# Do-an.net
KiCad netlist of a schematic drawn in Altium Designer
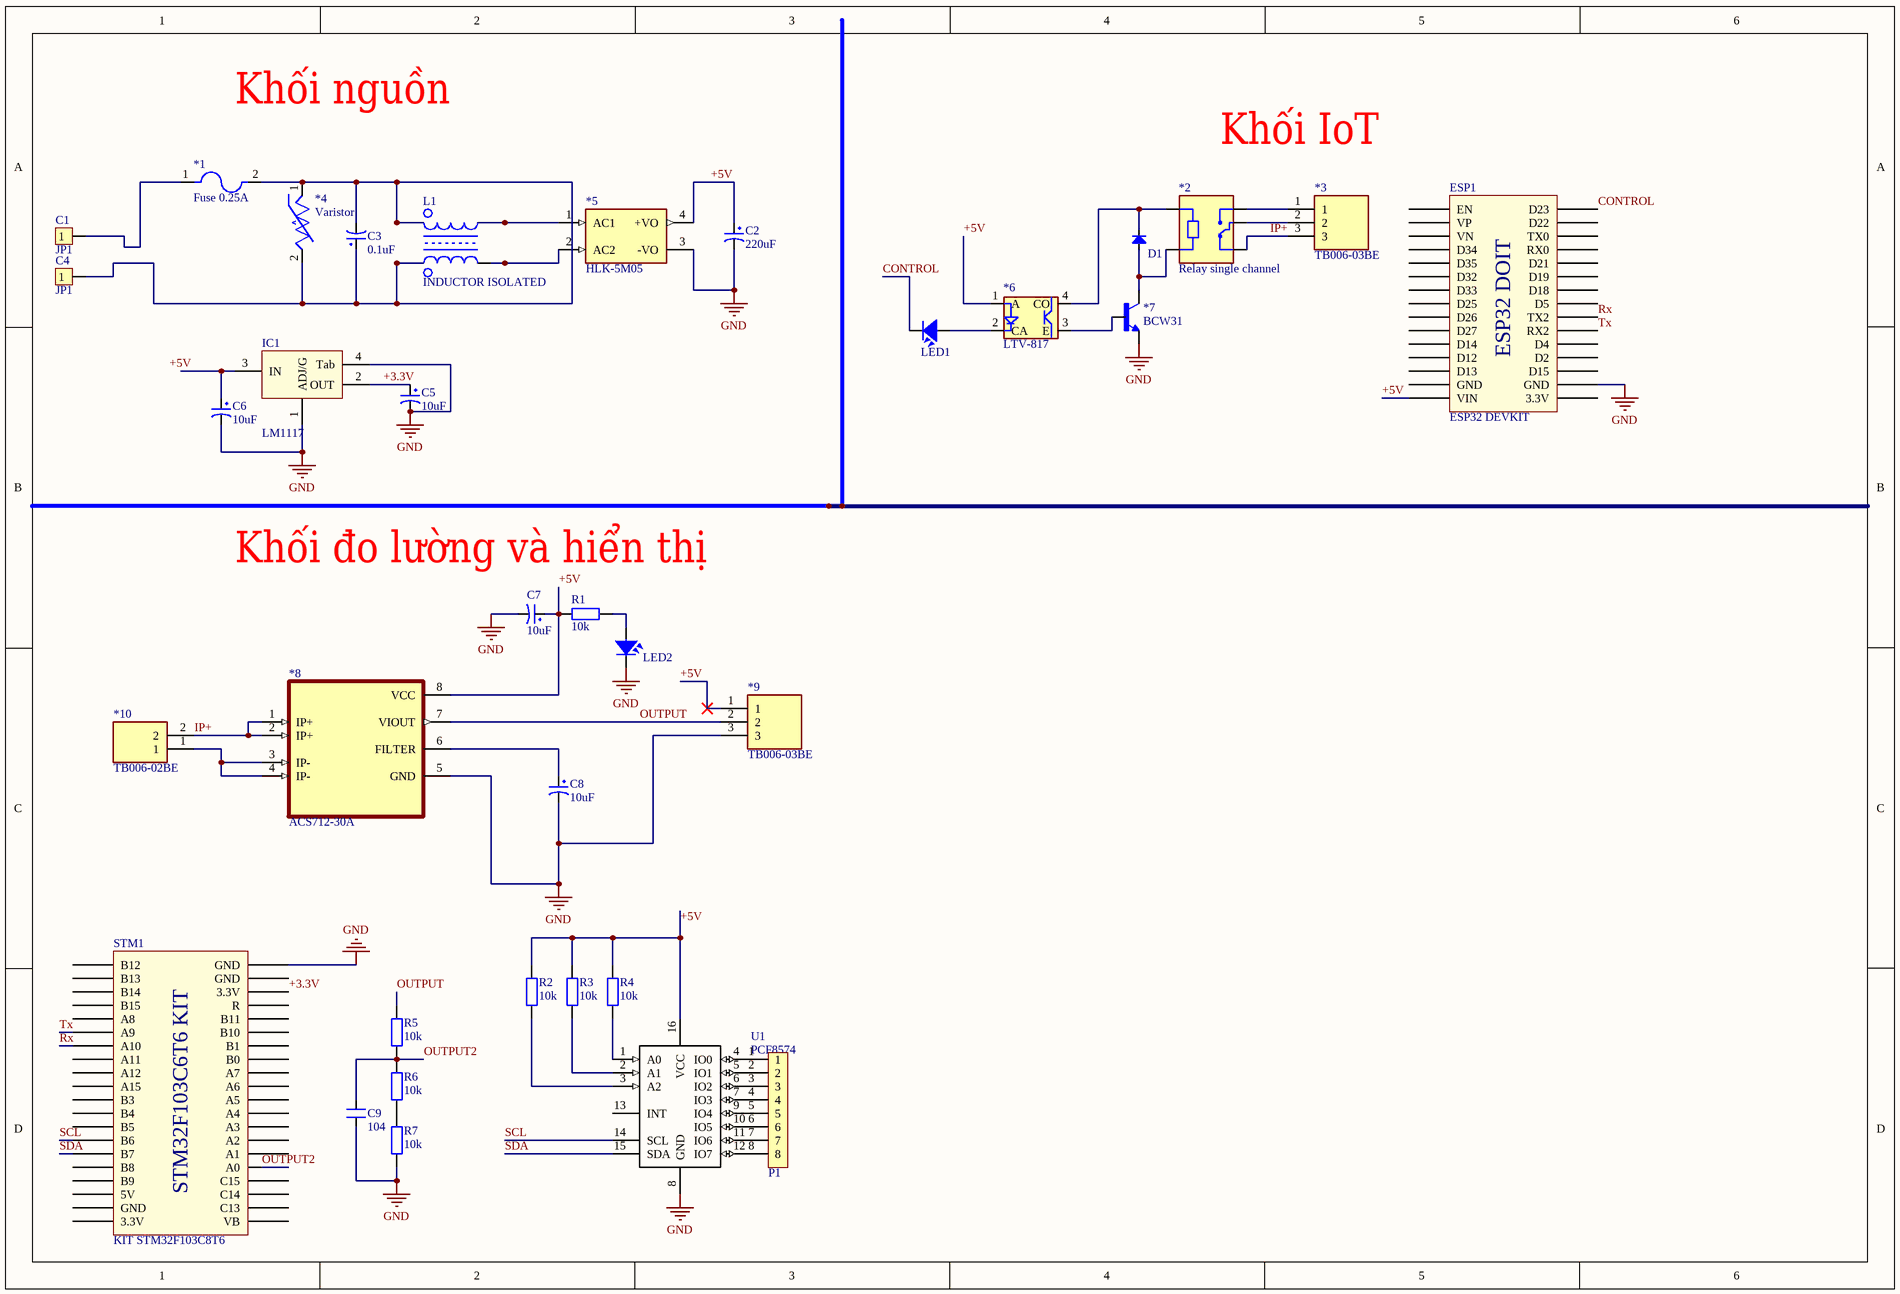
[diagram p0: Do-an.SchDoc]

(export (version "E")
  (design (tool "Eeschema 10.0.6"))
  (components
    (comp (ref "*1")
      (value "Fuse 0.25A")
      (footprint "FUSC6125X279N")
      (libsource (lib "KhanhBK_SCH_Library_2") (part "Fuse 0.25A"))
    )
    (comp (ref "*2")
      (value "Relay single channel")
      (footprint "RELAY_SRD-05VDC-SL-C")
      (libsource (lib "KhanhBK_SCH_Library_2") (part "Relay single channel"))
    )
    (comp (ref "*3")
      (value "TB006-03BE")
      (footprint "CUI_TB006 -508-03BE")
      (libsource (lib "KhanhBK_SCH_Library_2") (part "TB006-03BE"))
    )
    (comp (ref "*4")
      (value "Varistor")
      (footprint "VAR_B72220P3141K101")
      (libsource (lib "KhanhBK_SCH_Library_2") (part "Varistor"))
    )
    (comp (ref "*5")
      (value "HLK-5M05")
      (footprint "CONV_HLK-5M05")
      (libsource (lib "KhanhBK_SCH_Library_2") (part "HLK-5M05"))
    )
    (comp (ref "*6")
      (value "LTV-817")
      (footprint "LTV-817")
      (libsource (lib "KhanhBK_SCH_Library_2") (part "LTV-817"))
    )
    (comp (ref "*7")
      (value "BCW31")
      (footprint "SOT23-BEC")
      (libsource (lib "KhanhBK_SCH_Library_2") (part "BCW31"))
    )
    (comp (ref "*8")
      (value "ACS712-30A")
      (footprint "SOIC127P600X175-8N - duplicate")
      (libsource (lib "KhanhBK_SCH_Library_2") (part "ACS712-30A"))
    )
    (comp (ref "*9")
      (value "TB006-03BE")
      (footprint "CUI_TB006 -508-03BE")
      (libsource (lib "KhanhBK_SCH_Library_2") (part "TB006-03BE"))
    )
    (comp (ref "*10")
      (value "TB006-02BE")
      (footprint "CUI_TB006-508-02BE")
      (libsource (lib "KhanhBK_SCH_Library_2") (part "TB006-02BE"))
    )
    (comp (ref "C1")
      (value "JP1")
      (footprint "JP1-D1T")
      (description "WR-PHD 2.54 mm Angled Socket Header")
      (fields
        (field (name "MANUFACTURER") "Würth Elektronik eiSos GmbH")
        (field (name "PARTNO") "613002143121")
        (field (name "CREATED BY") "Karrer Zheng")
      )
      (libsource (lib "Do-an") (part "JP1"))
    )
    (comp (ref "C2")
      (value "220uF")
      (footprint "CP1.5/3.4")
      (description "Cap 100uF/35V - 470uF/16V")
      (libsource (lib "KhanhBK_SCH_Library_2") (part "CP3"))
    )
    (comp (ref "C3")
      (value "0.1uF")
      (footprint "CP1/2")
      (description "Cap P  0,1uF < 22uF , 16 - 50V")
      (libsource (lib "KhanhBK_SCH_Library_2") (part "CP1"))
    )
    (comp (ref "C4")
      (value "JP1")
      (footprint "JP1-D1T")
      (description "WR-PHD 2.54 mm Angled Socket Header")
      (fields
        (field (name "MANUFACTURER") "Würth Elektronik eiSos GmbH")
        (field (name "PARTNO") "613002143121")
        (field (name "CREATED BY") "Karrer Zheng")
      )
      (libsource (lib "KhanhBK_SCH_Library_1") (part "JP1"))
    )
    (comp (ref "C5")
      (value "10uF")
      (footprint "CP1/2")
      (description "Cap P  0,1uF < 22uF , 16 - 50V")
      (libsource (lib "KhanhBK_SCH_Library_2") (part "CP1"))
    )
    (comp (ref "C6")
      (value "10uF")
      (footprint "CP1/2")
      (description "Cap P  0,1uF < 22uF , 16 - 50V")
      (libsource (lib "KhanhBK_SCH_Library_2") (part "CP1"))
    )
    (comp (ref "C7")
      (value "10uF")
      (footprint "CP1/2")
      (description "Cap P  0,1uF < 22uF , 16 - 50V")
      (libsource (lib "") (part "CP1_1"))
    )
    (comp (ref "C8")
      (value "10uF")
      (footprint "CP1/2")
      (description "Cap P  0,1uF < 22uF , 16 - 50V")
      (libsource (lib "KhanhBK_SCH_Library_2") (part "CP1"))
    )
    (comp (ref "C9")
      (value "104")
      (footprint "CN2")
      (description "Cap np 104 => 105pF")
      (libsource (lib "KhanhBK_SCH_Library_2") (part "CN2"))
    )
    (comp (ref "D1")
      (value "Diode")
      (footprint "DIO-1A")
      (description "Default Diode")
      (fields (field (name "PUBLISHER") "Altium Limited"))
      (libsource (lib "KhanhBK_SCH_Library_2") (part "Diode"))
    )
    (comp (ref "ESP1")
      (value "ESP32 DEVKIT")
      (footprint "ESP32 WROOM 32 KIT")
      (libsource (lib "Module") (part "ESP32 WROOM 32 KIT"))
    )
    (comp (ref "IC1")
      (value "LM1117")
      (footprint "SOT223-4N")
      (description "3v3")
      (libsource (lib "KhanhBK_SCH_Library_2") (part "LM1117"))
    )
    (comp (ref "L1")
      (value "INDUCTOR ISOLATED")
      (footprint "INDUCTOR COMPACT")
      (libsource (lib "Devzone_SCHLib") (part "INDUCTOR ISOLATED"))
    )
    (comp (ref "LED1")
      (value "LED")
      (footprint "LED 3512")
      (libsource (lib "KhanhBK_SCH_Library_2") (part "LED SMD"))
    )
    (comp (ref "LED2")
      (value "LED")
      (footprint "LED-3MM-YELLOW")
      (description "LED Single colour Green and Red")
      (libsource (lib "KhanhBK_SCH_Library_1") (part "LED"))
    )
    (comp (ref "P1")
      (value "BIG Heager 8")
      (footprint "BIG_Header 8")
      (libsource (lib "KhanhBK_SCH_Library_2") (part "BIG_Header 8"))
    )
    (comp (ref "R1")
      (value "10k")
      (footprint "RES-1/4W")
      (description "Resistor 1/4W")
      (libsource (lib "KhanhBK_SCH_Library_2") (part "RES 1/4W"))
    )
    (comp (ref "R2")
      (value "10k")
      (footprint "RES-1/4W")
      (description "Resistor 1/4W")
      (libsource (lib "KhanhBK_SCH_Library_2") (part "RES 1/4W"))
    )
    (comp (ref "R3")
      (value "10k")
      (footprint "RES-1/4W")
      (description "Resistor 1/4W")
      (libsource (lib "KhanhBK_SCH_Library_2") (part "RES 1/4W"))
    )
    (comp (ref "R4")
      (value "10k")
      (footprint "RES-1/4W")
      (description "Resistor 1/4W")
      (libsource (lib "KhanhBK_SCH_Library_2") (part "RES 1/4W"))
    )
    (comp (ref "R5")
      (value "10k")
      (footprint "RES-1/4W")
      (description "Resistor 1/4W")
      (libsource (lib "KhanhBK_SCH_Library_2") (part "RES 1/4W"))
    )
    (comp (ref "R6")
      (value "10k")
      (footprint "RES-1/4W")
      (description "Resistor 1/4W")
      (libsource (lib "KhanhBK_SCH_Library_2") (part "RES 1/4W"))
    )
    (comp (ref "R7")
      (value "10k")
      (footprint "RES-1/4W")
      (description "Resistor 1/4W")
      (libsource (lib "KhanhBK_SCH_Library_2") (part "RES 1/4W"))
    )
    (comp (ref "STM1")
      (value "KIT STM32F103C8T6")
      (footprint "STM32F103 KIT")
      (description "KIT STM32F103C8T6 Bluepill")
      (libsource (lib "Module") (part "STM32f103 Bluepill"))
    )
    (comp (ref "U1")
      (value "PCF8574")
      (footprint "DIP16")
      (description "I2C PORT EXPANDER")
      (fields
        (field (name "MANUFACTURER PART NUMBER") "PCF8574T/3,512")
        (field (name "MANUFACTURER") "NXP Semiconductors")
      )
      (libsource (lib "KhanhBK_SCH_Library_2") (part "PCF8574"))
    )
  )
  (nets
    (net (code "1") (name "/+3.3V") (class "Default")
      (node (ref "C5") (pin "1") (pinfunction "1_1") (pintype "passive"))
      (node (ref "IC1") (pin "2") (pinfunction "OUT_2") (pintype "passive"))
      (node (ref "STM1") (pin "38") (pinfunction "3.3V_38") (pintype "passive"))
    )
    (net (code "2") (name "/+5V") (class "Default")
      (node (ref "*5") (pin "4") (pinfunction "+VO_4") (pintype "output"))
      (node (ref "*6") (pin "1") (pinfunction "A_1") (pintype "bidirectional"))
      (node (ref "*8") (pin "8") (pinfunction "VCC_8") (pintype "power_in"))
      (node (ref "*9") (pin "1") (pinfunction "1_1") (pintype "passive"))
      (node (ref "C2") (pin "1") (pinfunction "1_1") (pintype "passive"))
      (node (ref "C6") (pin "1") (pinfunction "1_1") (pintype "passive"))
      (node (ref "C7") (pin "1") (pinfunction "1_1") (pintype "passive"))
      (node (ref "ESP1") (pin "15") (pinfunction "VIN_15") (pintype "passive"))
      (node (ref "IC1") (pin "3") (pinfunction "IN_3") (pintype "passive"))
      (node (ref "R1") (pin "2") (pinfunction "2_2") (pintype "passive"))
      (node (ref "R2") (pin "2") (pinfunction "2_2") (pintype "passive"))
      (node (ref "R3") (pin "2") (pinfunction "2_2") (pintype "passive"))
      (node (ref "R4") (pin "2") (pinfunction "2_2") (pintype "passive"))
      (node (ref "U1") (pin "16") (pinfunction "VCC_16") (pintype "passive"))
    )
    (net (code "3") (name "/CONTROL") (class "Default")
      (node (ref "ESP1") (pin "30") (pinfunction "D23_30") (pintype "passive"))
      (node (ref "LED1") (pin "2") (pinfunction "2_2") (pintype "passive"))
    )
    (net (code "4") (name "/IP+") (class "Default")
      (node (ref "*10") (pin "2") (pinfunction "2_2") (pintype "passive"))
      (node (ref "*2") (pin "NC") (pinfunction "NC_NC") (pintype "passive"))
      (node (ref "*3") (pin "3") (pinfunction "3_3") (pintype "passive"))
      (node (ref "*8") (pin "1") (pinfunction "IP+_1") (pintype "input"))
      (node (ref "*8") (pin "2") (pinfunction "IP+_2") (pintype "input"))
    )
    (net (code "5") (name "/OUTPUT") (class "Default")
      (node (ref "*8") (pin "7") (pinfunction "VIOUT_7") (pintype "output"))
      (node (ref "*9") (pin "2") (pinfunction "2_2") (pintype "passive"))
      (node (ref "R5") (pin "2") (pinfunction "2_2") (pintype "passive"))
    )
    (net (code "6") (name "/OUTPUT2") (class "Default")
      (node (ref "C9") (pin "2") (pinfunction "2_2") (pintype "passive"))
      (node (ref "R5") (pin "1") (pinfunction "1_1") (pintype "passive"))
      (node (ref "R6") (pin "2") (pinfunction "2_2") (pintype "passive"))
      (node (ref "STM1") (pin "25") (pinfunction "A0_25") (pintype "passive"))
    )
    (net (code "7") (name "/Rx") (class "Default")
      (node (ref "ESP1") (pin "22") (pinfunction "TX2_22") (pintype "passive"))
      (node (ref "STM1") (pin "7") (pinfunction "A10_7") (pintype "passive"))
    )
    (net (code "8") (name "/SCL") (class "Default")
      (node (ref "STM1") (pin "14") (pinfunction "B6_14") (pintype "passive"))
      (node (ref "U1") (pin "14") (pinfunction "SCL_14") (pintype "open_collector"))
    )
    (net (code "9") (name "/SDA") (class "Default")
      (node (ref "STM1") (pin "15") (pinfunction "B7_15") (pintype "passive"))
      (node (ref "U1") (pin "15") (pinfunction "SDA_15") (pintype "open_collector"))
    )
    (net (code "10") (name "/Tx") (class "Default")
      (node (ref "ESP1") (pin "21") (pinfunction "RX2_21") (pintype "passive"))
      (node (ref "STM1") (pin "6") (pinfunction "A9_6") (pintype "passive"))
    )
    (net (code "11") (name "GND") (class "Default")
      (node (ref "*5") (pin "3") (pinfunction "-VO_3") (pintype "passive"))
      (node (ref "*7") (pin "E") (pinfunction "E_E") (pintype "passive"))
      (node (ref "*8") (pin "5") (pinfunction "GND_5") (pintype "power_in"))
      (node (ref "*9") (pin "3") (pinfunction "3_3") (pintype "passive"))
      (node (ref "C2") (pin "2") (pinfunction "2_2") (pintype "passive"))
      (node (ref "C5") (pin "2") (pinfunction "2_2") (pintype "passive"))
      (node (ref "C6") (pin "2") (pinfunction "2_2") (pintype "passive"))
      (node (ref "C7") (pin "2") (pinfunction "2_2") (pintype "passive"))
      (node (ref "C8") (pin "2") (pinfunction "2_2") (pintype "passive"))
      (node (ref "C9") (pin "1") (pinfunction "1_1") (pintype "passive"))
      (node (ref "ESP1") (pin "17") (pinfunction "GND_17") (pintype "passive"))
      (node (ref "IC1") (pin "1") (pinfunction "ADJ/G_1") (pintype "passive"))
      (node (ref "IC1") (pin "4") (pinfunction "Tab_4") (pintype "passive"))
      (node (ref "LED2") (pin "2") (pinfunction "2_2") (pintype "passive"))
      (node (ref "R7") (pin "1") (pinfunction "1_1") (pintype "passive"))
      (node (ref "STM1") (pin "40") (pinfunction "GND_40") (pintype "passive"))
      (node (ref "U1") (pin "8") (pinfunction "GND_8") (pintype "power_in"))
    )
    (net (code "12") (name "Net-(*1-Pad1)") (class "Default")
      (node (ref "*1") (pin "1") (pinfunction "1_1") (pintype "passive"))
      (node (ref "C1") (pin "1") (pinfunction "1_1") (pintype "passive"))
    )
    (net (code "13") (name "Net-(*1-Pad2)") (class "Default")
      (node (ref "*1") (pin "2") (pinfunction "2_2") (pintype "passive"))
      (node (ref "*4") (pin "1") (pinfunction "1_1") (pintype "passive"))
      (node (ref "*4") (pin "2") (pinfunction "2_2") (pintype "passive"))
      (node (ref "C3") (pin "1") (pinfunction "1_1") (pintype "passive"))
      (node (ref "C3") (pin "2") (pinfunction "2_2") (pintype "passive"))
      (node (ref "C4") (pin "1") (pinfunction "1_1") (pintype "passive"))
      (node (ref "L1") (pin "1") (pinfunction "1_1") (pintype "passive"))
      (node (ref "L1") (pin "3") (pinfunction "3_3") (pintype "passive"))
    )
    (net (code "14") (name "Net-(*2-PadCOM)") (class "Default")
      (node (ref "*2") (pin "COM") (pinfunction "COM_COM") (pintype "passive"))
      (node (ref "*3") (pin "2") (pinfunction "2_2") (pintype "passive"))
    )
    (net (code "15") (name "Net-(*2-PadNO)") (class "Default")
      (node (ref "*2") (pin "NO") (pinfunction "NO_NO") (pintype "passive"))
      (node (ref "*3") (pin "1") (pinfunction "1_1") (pintype "passive"))
    )
    (net (code "16") (name "Net-(*5-AC1)") (class "Default")
      (node (ref "*5") (pin "1") (pinfunction "AC1_1") (pintype "input"))
      (node (ref "L1") (pin "4") (pinfunction "4_4") (pintype "passive"))
    )
    (net (code "17") (name "Net-(*5-AC2)") (class "Default")
      (node (ref "*5") (pin "2") (pinfunction "AC2_2") (pintype "input"))
      (node (ref "L1") (pin "2") (pinfunction "2_2") (pintype "passive"))
    )
    (net (code "18") (name "Net-(*6-CA)") (class "Default")
      (node (ref "*6") (pin "2") (pinfunction "CA_2") (pintype "bidirectional"))
      (node (ref "LED1") (pin "1") (pinfunction "1_1") (pintype "passive"))
    )
    (net (code "19") (name "Net-(*6-CO)") (class "Default")
      (node (ref "*2") (pin "A1") (pinfunction "A1_A1") (pintype "passive"))
      (node (ref "*6") (pin "4") (pinfunction "CO_4") (pintype "bidirectional"))
      (node (ref "D1") (pin "2") (pinfunction "K_2") (pintype "passive"))
    )
    (net (code "20") (name "Net-(*6-E)") (class "Default")
      (node (ref "*6") (pin "3") (pinfunction "E_3") (pintype "bidirectional"))
      (node (ref "*7") (pin "B") (pinfunction "B_B") (pintype "passive"))
    )
    (net (code "21") (name "Net-(*8-FILTER)") (class "Default")
      (node (ref "*8") (pin "6") (pinfunction "FILTER_6") (pintype "passive"))
      (node (ref "C8") (pin "1") (pinfunction "1_1") (pintype "passive"))
    )
    (net (code "22") (name "Net-(*10-Pad1)") (class "Default")
      (node (ref "*10") (pin "1") (pinfunction "1_1") (pintype "passive"))
      (node (ref "*8") (pin "3") (pinfunction "IP-_3") (pintype "input"))
      (node (ref "*8") (pin "4") (pinfunction "IP-_4") (pintype "input"))
    )
    (net (code "23") (name "Net-(D1-A)") (class "Default")
      (node (ref "*2") (pin "A2") (pinfunction "A2_A2") (pintype "passive"))
      (node (ref "*7") (pin "C") (pinfunction "C_C") (pintype "passive"))
      (node (ref "D1") (pin "1") (pinfunction "A_1") (pintype "passive"))
    )
    (net (code "24") (name "Net-(LED2-Pad1)") (class "Default")
      (node (ref "LED2") (pin "1") (pinfunction "1_1") (pintype "passive"))
      (node (ref "R1") (pin "1") (pinfunction "1_1") (pintype "passive"))
    )
    (net (code "25") (name "Net-(R6-Pad1)") (class "Default")
      (node (ref "R6") (pin "1") (pinfunction "1_1") (pintype "passive"))
      (node (ref "R7") (pin "2") (pinfunction "2_2") (pintype "passive"))
    )
    (net (code "26") (name "Net-(U1-A0)") (class "Default")
      (node (ref "R4") (pin "1") (pinfunction "1_1") (pintype "passive"))
      (node (ref "U1") (pin "1") (pinfunction "A0_1") (pintype "input"))
    )
    (net (code "27") (name "Net-(U1-A1)") (class "Default")
      (node (ref "R3") (pin "1") (pinfunction "1_1") (pintype "passive"))
      (node (ref "U1") (pin "2") (pinfunction "A1_2") (pintype "input"))
    )
    (net (code "28") (name "Net-(U1-A2)") (class "Default")
      (node (ref "R2") (pin "1") (pinfunction "1_1") (pintype "passive"))
      (node (ref "U1") (pin "3") (pinfunction "A2_3") (pintype "input"))
    )
    (net (code "29") (name "Net-(U1-IO0)") (class "Default")
      (node (ref "P1") (pin "1") (pinfunction "1_1") (pintype "passive"))
      (node (ref "U1") (pin "4") (pinfunction "IO0_4") (pintype "bidirectional"))
    )
    (net (code "30") (name "Net-(U1-IO1)") (class "Default")
      (node (ref "P1") (pin "2") (pinfunction "2_2") (pintype "passive"))
      (node (ref "U1") (pin "5") (pinfunction "IO1_5") (pintype "bidirectional"))
    )
    (net (code "31") (name "Net-(U1-IO2)") (class "Default")
      (node (ref "P1") (pin "3") (pinfunction "3_3") (pintype "passive"))
      (node (ref "U1") (pin "6") (pinfunction "IO2_6") (pintype "bidirectional"))
    )
    (net (code "32") (name "Net-(U1-IO3)") (class "Default")
      (node (ref "P1") (pin "4") (pinfunction "4_4") (pintype "passive"))
      (node (ref "U1") (pin "7") (pinfunction "IO3_7") (pintype "bidirectional"))
    )
    (net (code "33") (name "Net-(U1-IO4)") (class "Default")
      (node (ref "P1") (pin "5") (pinfunction "5_5") (pintype "passive"))
      (node (ref "U1") (pin "9") (pinfunction "IO4_9") (pintype "bidirectional"))
    )
    (net (code "34") (name "Net-(U1-IO5)") (class "Default")
      (node (ref "P1") (pin "6") (pinfunction "6_6") (pintype "passive"))
      (node (ref "U1") (pin "10") (pinfunction "IO5_10") (pintype "bidirectional"))
    )
    (net (code "35") (name "Net-(U1-IO6)") (class "Default")
      (node (ref "P1") (pin "7") (pinfunction "7_7") (pintype "passive"))
      (node (ref "U1") (pin "11") (pinfunction "IO6_11") (pintype "bidirectional"))
    )
    (net (code "36") (name "Net-(U1-IO7)") (class "Default")
      (node (ref "P1") (pin "8") (pinfunction "8_8") (pintype "passive"))
      (node (ref "U1") (pin "12") (pinfunction "IO7_12") (pintype "bidirectional"))
    )
    (net (code "37") (name "unconnected-(ESP1-3.3V-Pad16)") (class "Default")
      (node (ref "ESP1") (pin "16") (pinfunction "3.3V_16") (pintype "passive"))
    )
    (net (code "38") (name "unconnected-(ESP1-D2-Pad19)") (class "Default")
      (node (ref "ESP1") (pin "19") (pinfunction "D2_19") (pintype "passive"))
    )
    (net (code "39") (name "unconnected-(ESP1-D4-Pad20)") (class "Default")
      (node (ref "ESP1") (pin "20") (pinfunction "D4_20") (pintype "passive"))
    )
    (net (code "40") (name "unconnected-(ESP1-D5-Pad23)") (class "Default")
      (node (ref "ESP1") (pin "23") (pinfunction "D5_23") (pintype "passive"))
    )
    (net (code "41") (name "unconnected-(ESP1-D12-Pad12)") (class "Default")
      (node (ref "ESP1") (pin "12") (pinfunction "D12_12") (pintype "passive"))
    )
    (net (code "42") (name "unconnected-(ESP1-D13-Pad13)") (class "Default")
      (node (ref "ESP1") (pin "13") (pinfunction "D13_13") (pintype "passive"))
    )
    (net (code "43") (name "unconnected-(ESP1-D14-Pad11)") (class "Default")
      (node (ref "ESP1") (pin "11") (pinfunction "D14_11") (pintype "passive"))
    )
    (net (code "44") (name "unconnected-(ESP1-D15-Pad18)") (class "Default")
      (node (ref "ESP1") (pin "18") (pinfunction "D15_18") (pintype "passive"))
    )
    (net (code "45") (name "unconnected-(ESP1-D18-Pad24)") (class "Default")
      (node (ref "ESP1") (pin "24") (pinfunction "D18_24") (pintype "passive"))
    )
    (net (code "46") (name "unconnected-(ESP1-D19-Pad25)") (class "Default")
      (node (ref "ESP1") (pin "25") (pinfunction "D19_25") (pintype "passive"))
    )
    (net (code "47") (name "unconnected-(ESP1-D21-Pad26)") (class "Default")
      (node (ref "ESP1") (pin "26") (pinfunction "D21_26") (pintype "passive"))
    )
    (net (code "48") (name "unconnected-(ESP1-D22-Pad29)") (class "Default")
      (node (ref "ESP1") (pin "29") (pinfunction "D22_29") (pintype "passive"))
    )
    (net (code "49") (name "unconnected-(ESP1-D25-Pad8)") (class "Default")
      (node (ref "ESP1") (pin "8") (pinfunction "D25_8") (pintype "passive"))
    )
    (net (code "50") (name "unconnected-(ESP1-D26-Pad9)") (class "Default")
      (node (ref "ESP1") (pin "9") (pinfunction "D26_9") (pintype "passive"))
    )
    (net (code "51") (name "unconnected-(ESP1-D27-Pad10)") (class "Default")
      (node (ref "ESP1") (pin "10") (pinfunction "D27_10") (pintype "passive"))
    )
    (net (code "52") (name "unconnected-(ESP1-D32-Pad6)") (class "Default")
      (node (ref "ESP1") (pin "6") (pinfunction "D32_6") (pintype "passive"))
    )
    (net (code "53") (name "unconnected-(ESP1-D33-Pad7)") (class "Default")
      (node (ref "ESP1") (pin "7") (pinfunction "D33_7") (pintype "passive"))
    )
    (net (code "54") (name "unconnected-(ESP1-D34-Pad4)") (class "Default")
      (node (ref "ESP1") (pin "4") (pinfunction "D34_4") (pintype "passive"))
    )
    (net (code "55") (name "unconnected-(ESP1-D35-Pad5)") (class "Default")
      (node (ref "ESP1") (pin "5") (pinfunction "D35_5") (pintype "passive"))
    )
    (net (code "56") (name "unconnected-(ESP1-EN-Pad1)") (class "Default")
      (node (ref "ESP1") (pin "1") (pinfunction "EN_1") (pintype "passive"))
    )
    (net (code "57") (name "unconnected-(ESP1-GND-Pad14)") (class "Default")
      (node (ref "ESP1") (pin "14") (pinfunction "GND_14") (pintype "passive"))
    )
    (net (code "58") (name "unconnected-(ESP1-RX0-Pad27)") (class "Default")
      (node (ref "ESP1") (pin "27") (pinfunction "RX0_27") (pintype "passive"))
    )
    (net (code "59") (name "unconnected-(ESP1-TX0-Pad28)") (class "Default")
      (node (ref "ESP1") (pin "28") (pinfunction "TX0_28") (pintype "passive"))
    )
    (net (code "60") (name "unconnected-(ESP1-VN-Pad3)") (class "Default")
      (node (ref "ESP1") (pin "3") (pinfunction "VN_3") (pintype "passive"))
    )
    (net (code "61") (name "unconnected-(ESP1-VP-Pad2)") (class "Default")
      (node (ref "ESP1") (pin "2") (pinfunction "VP_2") (pintype "passive"))
    )
    (net (code "62") (name "unconnected-(STM1-3.3V-Pad20)") (class "Default")
      (node (ref "STM1") (pin "20") (pinfunction "3.3V_20") (pintype "passive"))
    )
    (net (code "63") (name "unconnected-(STM1-5V-Pad18)") (class "Default")
      (node (ref "STM1") (pin "18") (pinfunction "5V_18") (pintype "passive"))
    )
    (net (code "64") (name "unconnected-(STM1-A1-Pad26)") (class "Default")
      (node (ref "STM1") (pin "26") (pinfunction "A1_26") (pintype "passive"))
    )
    (net (code "65") (name "unconnected-(STM1-A2-Pad27)") (class "Default")
      (node (ref "STM1") (pin "27") (pinfunction "A2_27") (pintype "passive"))
    )
    (net (code "66") (name "unconnected-(STM1-A3-Pad28)") (class "Default")
      (node (ref "STM1") (pin "28") (pinfunction "A3_28") (pintype "passive"))
    )
    (net (code "67") (name "unconnected-(STM1-A4-Pad29)") (class "Default")
      (node (ref "STM1") (pin "29") (pinfunction "A4_29") (pintype "passive"))
    )
    (net (code "68") (name "unconnected-(STM1-A5-Pad30)") (class "Default")
      (node (ref "STM1") (pin "30") (pinfunction "A5_30") (pintype "passive"))
    )
    (net (code "69") (name "unconnected-(STM1-A6-Pad31)") (class "Default")
      (node (ref "STM1") (pin "31") (pinfunction "A6_31") (pintype "passive"))
    )
    (net (code "70") (name "unconnected-(STM1-A7-Pad32)") (class "Default")
      (node (ref "STM1") (pin "32") (pinfunction "A7_32") (pintype "passive"))
    )
    (net (code "71") (name "unconnected-(STM1-A8-Pad5)") (class "Default")
      (node (ref "STM1") (pin "5") (pinfunction "A8_5") (pintype "passive"))
    )
    (net (code "72") (name "unconnected-(STM1-A11-Pad8)") (class "Default")
      (node (ref "STM1") (pin "8") (pinfunction "A11_8") (pintype "passive"))
    )
    (net (code "73") (name "unconnected-(STM1-A12-Pad9)") (class "Default")
      (node (ref "STM1") (pin "9") (pinfunction "A12_9") (pintype "passive"))
    )
    (net (code "74") (name "unconnected-(STM1-A15-Pad10)") (class "Default")
      (node (ref "STM1") (pin "10") (pinfunction "A15_10") (pintype "passive"))
    )
    (net (code "75") (name "unconnected-(STM1-B0-Pad33)") (class "Default")
      (node (ref "STM1") (pin "33") (pinfunction "B0_33") (pintype "passive"))
    )
    (net (code "76") (name "unconnected-(STM1-B1-Pad34)") (class "Default")
      (node (ref "STM1") (pin "34") (pinfunction "B1_34") (pintype "passive"))
    )
    (net (code "77") (name "unconnected-(STM1-B3-Pad11)") (class "Default")
      (node (ref "STM1") (pin "11") (pinfunction "B3_11") (pintype "passive"))
    )
    (net (code "78") (name "unconnected-(STM1-B4-Pad12)") (class "Default")
      (node (ref "STM1") (pin "12") (pinfunction "B4_12") (pintype "passive"))
    )
    (net (code "79") (name "unconnected-(STM1-B5-Pad13)") (class "Default")
      (node (ref "STM1") (pin "13") (pinfunction "B5_13") (pintype "passive"))
    )
    (net (code "80") (name "unconnected-(STM1-B8-Pad16)") (class "Default")
      (node (ref "STM1") (pin "16") (pinfunction "B8_16") (pintype "passive"))
    )
    (net (code "81") (name "unconnected-(STM1-B9-Pad17)") (class "Default")
      (node (ref "STM1") (pin "17") (pinfunction "B9_17") (pintype "passive"))
    )
    (net (code "82") (name "unconnected-(STM1-B10-Pad35)") (class "Default")
      (node (ref "STM1") (pin "35") (pinfunction "B10_35") (pintype "passive"))
    )
    (net (code "83") (name "unconnected-(STM1-B11-Pad36)") (class "Default")
      (node (ref "STM1") (pin "36") (pinfunction "B11_36") (pintype "passive"))
    )
    (net (code "84") (name "unconnected-(STM1-B12-Pad1)") (class "Default")
      (node (ref "STM1") (pin "1") (pinfunction "B12_1") (pintype "passive"))
    )
    (net (code "85") (name "unconnected-(STM1-B13-Pad2)") (class "Default")
      (node (ref "STM1") (pin "2") (pinfunction "B13_2") (pintype "passive"))
    )
    (net (code "86") (name "unconnected-(STM1-B14-Pad3)") (class "Default")
      (node (ref "STM1") (pin "3") (pinfunction "B14_3") (pintype "passive"))
    )
    (net (code "87") (name "unconnected-(STM1-B15-Pad4)") (class "Default")
      (node (ref "STM1") (pin "4") (pinfunction "B15_4") (pintype "passive"))
    )
    (net (code "88") (name "unconnected-(STM1-C13-Pad22)") (class "Default")
      (node (ref "STM1") (pin "22") (pinfunction "C13_22") (pintype "passive"))
    )
    (net (code "89") (name "unconnected-(STM1-C14-Pad23)") (class "Default")
      (node (ref "STM1") (pin "23") (pinfunction "C14_23") (pintype "passive"))
    )
    (net (code "90") (name "unconnected-(STM1-C15-Pad24)") (class "Default")
      (node (ref "STM1") (pin "24") (pinfunction "C15_24") (pintype "passive"))
    )
    (net (code "91") (name "unconnected-(STM1-GND-Pad19)") (class "Default")
      (node (ref "STM1") (pin "19") (pinfunction "GND_19") (pintype "passive"))
    )
    (net (code "92") (name "unconnected-(STM1-GND-Pad39)") (class "Default")
      (node (ref "STM1") (pin "39") (pinfunction "GND_39") (pintype "passive"))
    )
    (net (code "93") (name "unconnected-(STM1-R-Pad37)") (class "Default")
      (node (ref "STM1") (pin "37") (pinfunction "R_37") (pintype "passive"))
    )
    (net (code "94") (name "unconnected-(STM1-VB-Pad21)") (class "Default")
      (node (ref "STM1") (pin "21") (pinfunction "VB_21") (pintype "passive"))
    )
    (net (code "95") (name "unconnected-(U1-INT-Pad13)") (class "Default")
      (node (ref "U1") (pin "13") (pinfunction "INT_13") (pintype "open_collector"))
    )
  )
)
